# Taschenlampe_LX_V1_0.net
KiCad netlist of a schematic drawn in EAGLE
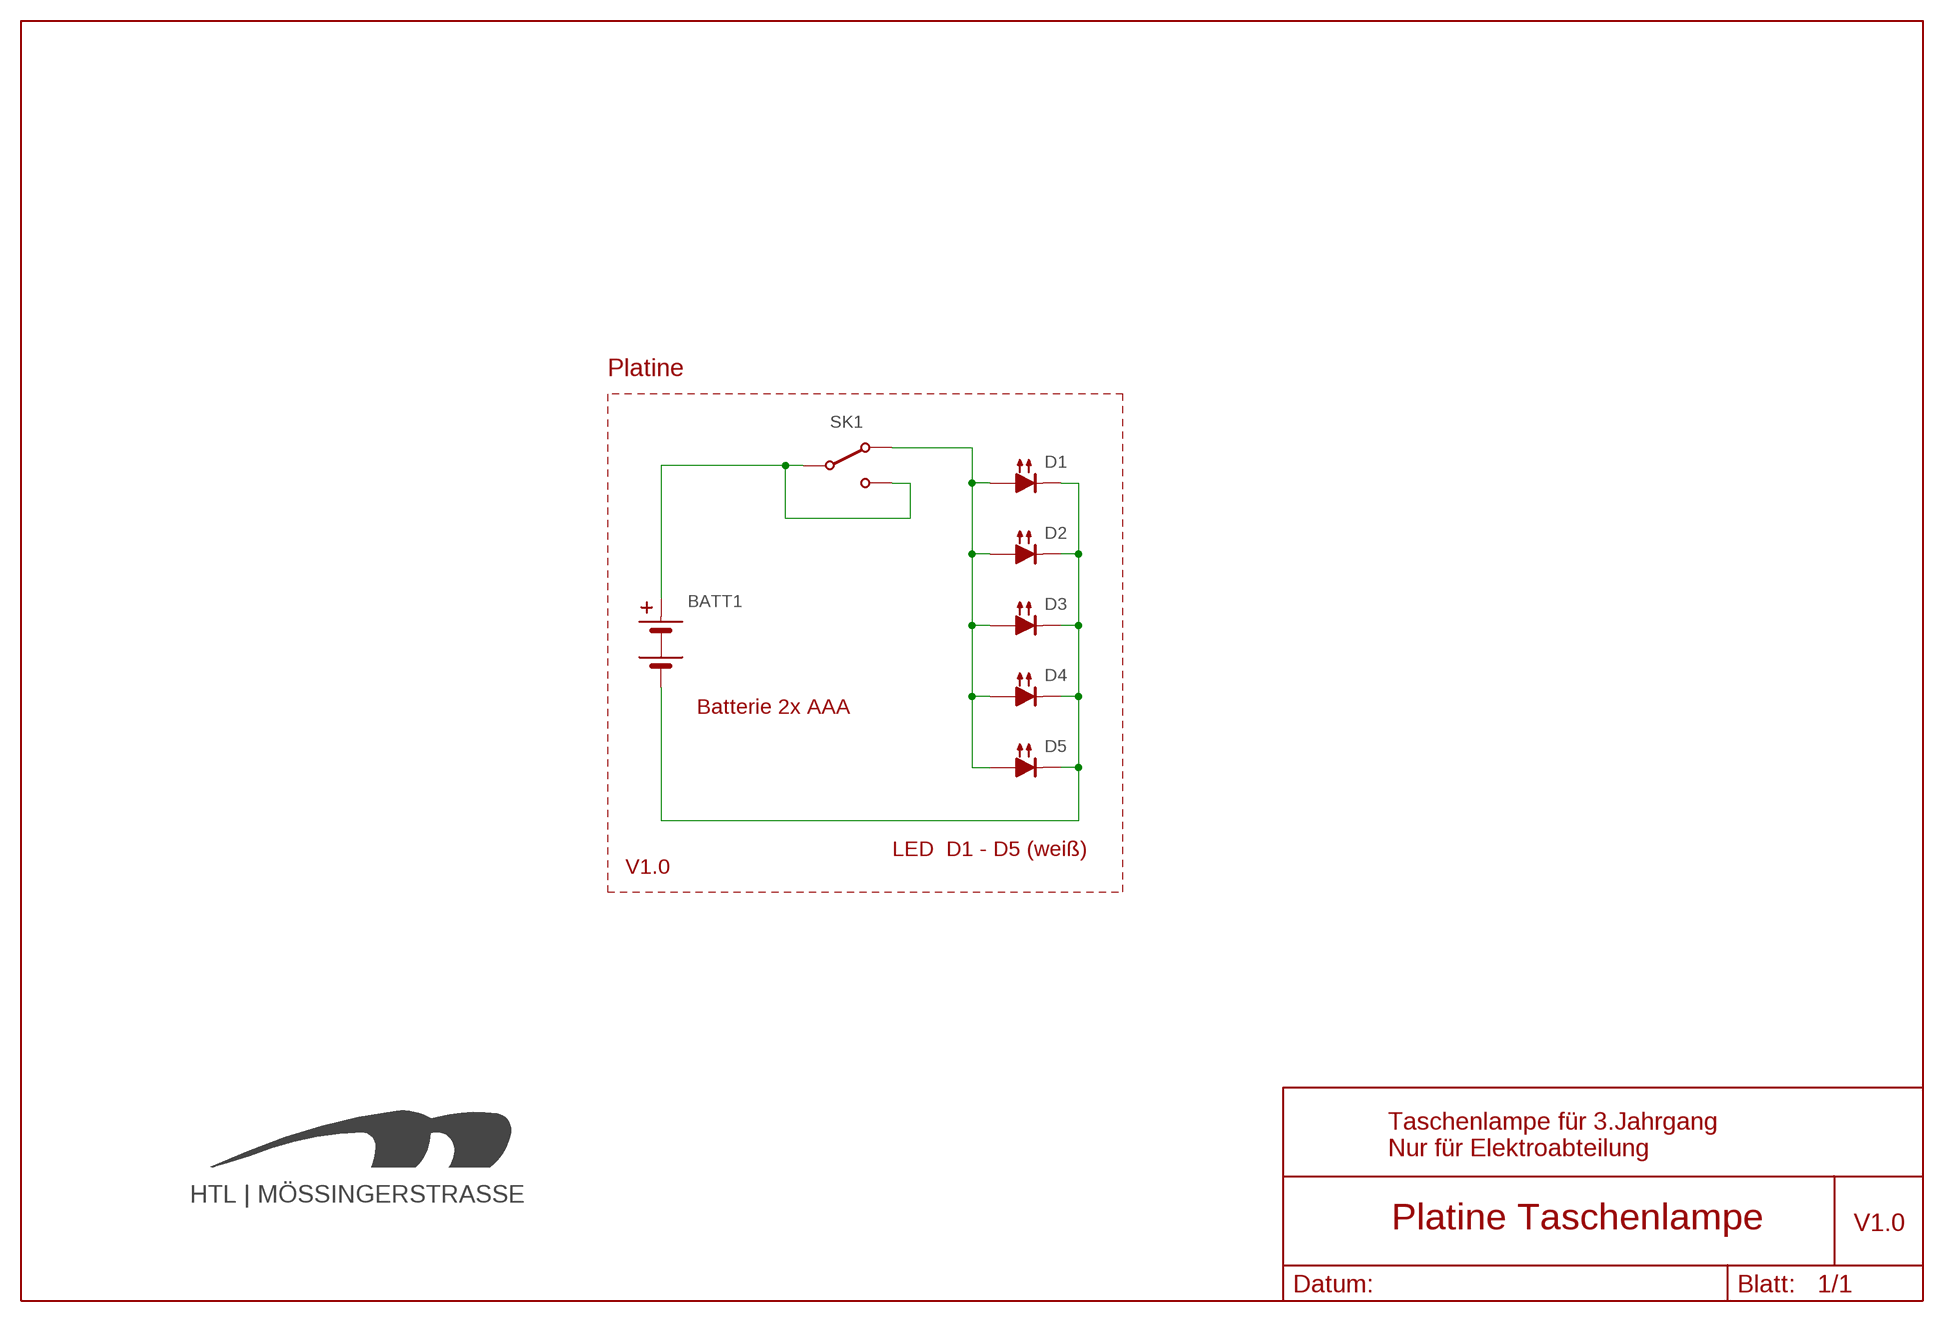
[diagram p0: schematic, sheet 1]

(export (version "E")
  (design (tool "Eeschema 10.0.6"))
  (components
    (comp (ref "BATT1")
      (value "BATTERIEHALTER_2X_AAA")
      (footprint "eagle-import:BATTERIEHALTER")
      (libsource (lib "eagle-import") (part "BATTERIEHALTER_2X_AAA"))
    )
    (comp (ref "D1")
      (value "LEUCHTDIODE_DIN_ALT")
      (footprint "eagle-import:LEUCHTDIODE")
      (libsource (lib "eagle-import") (part "LEUCHTDIODE_DIN_ALT"))
    )
    (comp (ref "D2")
      (value "LEUCHTDIODE_DIN_ALT")
      (footprint "eagle-import:LEUCHTDIODE")
      (libsource (lib "eagle-import") (part "LEUCHTDIODE_DIN_ALT"))
    )
    (comp (ref "D3")
      (value "LEUCHTDIODE_DIN_ALT")
      (footprint "eagle-import:LEUCHTDIODE")
      (libsource (lib "eagle-import") (part "LEUCHTDIODE_DIN_ALT"))
    )
    (comp (ref "D4")
      (value "LEUCHTDIODE_DIN_ALT")
      (footprint "eagle-import:LEUCHTDIODE")
      (libsource (lib "eagle-import") (part "LEUCHTDIODE_DIN_ALT"))
    )
    (comp (ref "D5")
      (value "LEUCHTDIODE_DIN_ALT")
      (footprint "eagle-import:LEUCHTDIODE")
      (libsource (lib "eagle-import") (part "LEUCHTDIODE_DIN_ALT"))
    )
    (comp (ref "SK1")
      (value "SCHALTER")
      (footprint "eagle-import:SCHALTER")
      (libsource (lib "eagle-import") (part "SCHALTER"))
    )
    (comp (ref "U$2")
      (value "HTL_LOGOBOT_15MM")
      (footprint "eagle-import:LOGOBOT_15")
      (libsource (lib "eagle-import") (part "HTL_LOGOBOT_15MM"))
    )
  )
  (nets
    (net (code "1") (name "Net-(BATT1-PadP-)") (class "Default")
      (node (ref "BATT1") (pin "P-") (pinfunction "P-_P-") (pintype "bidirectional"))
      (node (ref "D1") (pin "K") (pinfunction "K_K") (pintype "passive"))
      (node (ref "D2") (pin "K") (pinfunction "K_K") (pintype "passive"))
      (node (ref "D3") (pin "K") (pinfunction "K_K") (pintype "passive"))
      (node (ref "D4") (pin "K") (pinfunction "K_K") (pintype "passive"))
      (node (ref "D5") (pin "K") (pinfunction "K_K") (pintype "passive"))
    )
    (net (code "2") (name "Net-(SK1-P$1)") (class "Default")
      (node (ref "D1") (pin "A") (pinfunction "A_A") (pintype "passive"))
      (node (ref "D2") (pin "A") (pinfunction "A_A") (pintype "passive"))
      (node (ref "D3") (pin "A") (pinfunction "A_A") (pintype "passive"))
      (node (ref "D4") (pin "A") (pinfunction "A_A") (pintype "passive"))
      (node (ref "D5") (pin "A") (pinfunction "A_A") (pintype "passive"))
      (node (ref "SK1") (pin "P1") (pinfunction "P$1_P1") (pintype "bidirectional"))
    )
    (net (code "3") (name "Net-(SK1-P$2)") (class "Default")
      (node (ref "BATT1") (pin "P+") (pinfunction "P+_P+") (pintype "bidirectional"))
      (node (ref "SK1") (pin "P") (pinfunction "P_P") (pintype "bidirectional"))
      (node (ref "SK1") (pin "P2") (pinfunction "P$2_P2") (pintype "bidirectional"))
    )
  )
)
